# mcu.net
KiCad netlist of a schematic drawn in Altium Designer
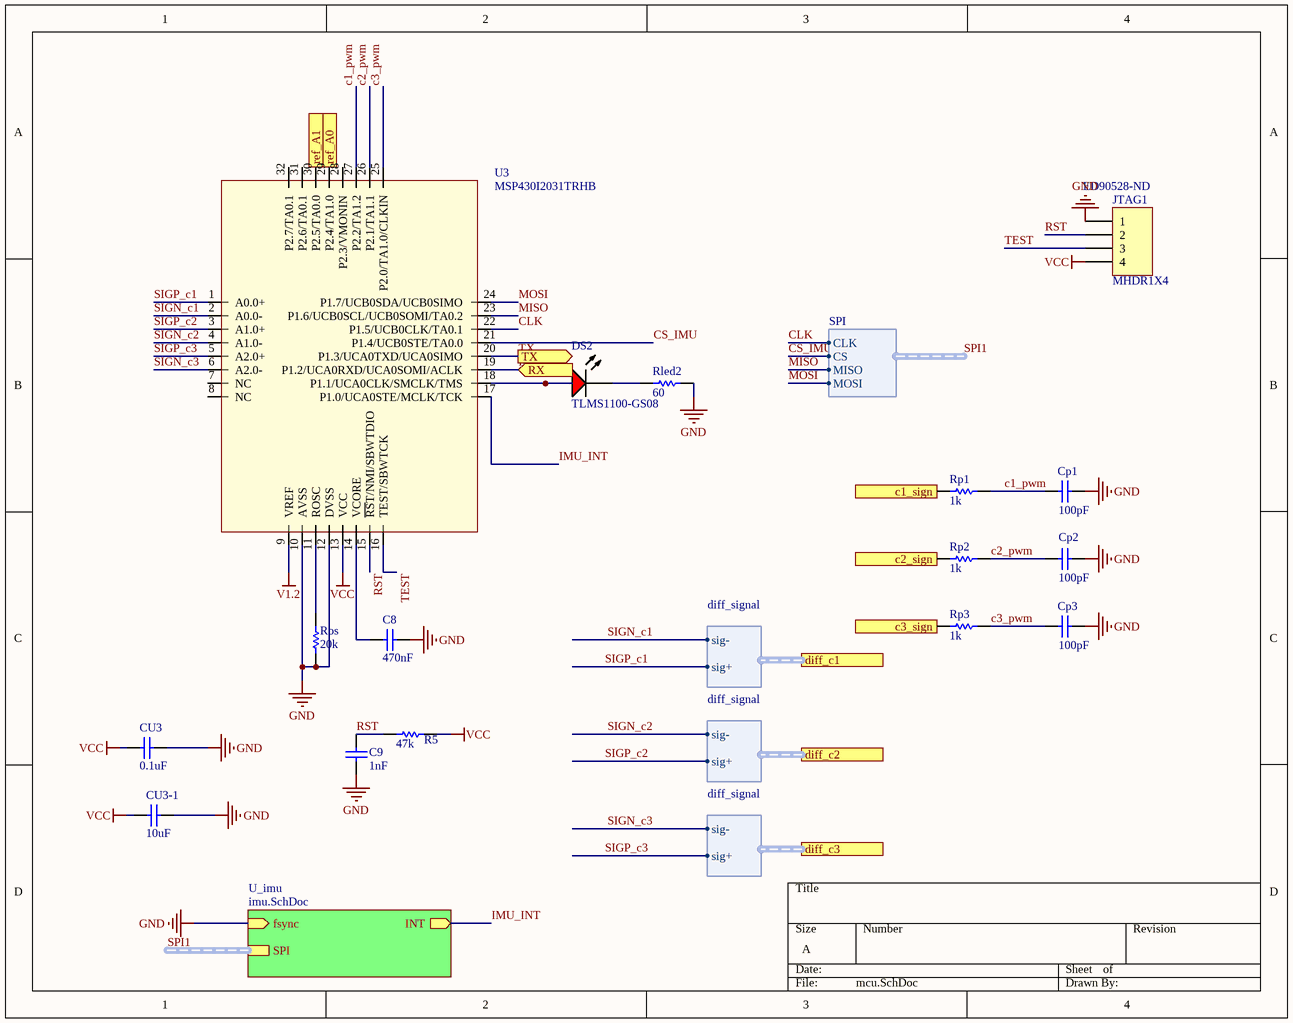
[diagram p0: mcu.SchDoc]

(export (version "E")
  (design (tool "Eeschema 10.0.6"))
  (components
    (comp (ref "C8")
      (value "470nF")
      (footprint "0402")
      (description "Ceramic Capacitor (Surface Mount)")
      (fields (field (name "MANUFACTURER") "Generic Ceramic Chip Cap (TBD)") (field (name "Comment") "Cap"))
      (libsource (lib "maglib") (part "Cap"))
    )
    (comp (ref "C9")
      (value "1nF")
      (footprint "0402")
      (description "Ceramic Capacitor (Surface Mount)")
      (fields (field (name "MANUFACTURER") "Generic Ceramic Chip Cap (TBD)") (field (name "Comment") "Cap"))
      (libsource (lib "maglib") (part "Cap"))
    )
    (comp (ref "Cp1")
      (value "100pF")
      (footprint "0402")
      (description "Ceramic Capacitor (Surface Mount)")
      (fields (field (name "MANUFACTURER") "Generic Ceramic Chip Cap (TBD)") (field (name "Comment") "Cap"))
      (libsource (lib "maglib") (part "Cap"))
    )
    (comp (ref "Cp2")
      (value "100pF")
      (footprint "0402")
      (description "Ceramic Capacitor (Surface Mount)")
      (fields (field (name "MANUFACTURER") "Generic Ceramic Chip Cap (TBD)") (field (name "Comment") "Cap"))
      (libsource (lib "maglib") (part "Cap"))
    )
    (comp (ref "Cp3")
      (value "100pF")
      (footprint "0402")
      (description "Ceramic Capacitor (Surface Mount)")
      (fields (field (name "MANUFACTURER") "Generic Ceramic Chip Cap (TBD)") (field (name "Comment") "Cap"))
      (libsource (lib "maglib") (part "Cap"))
    )
    (comp (ref "CU3")
      (value "0.1uF")
      (footprint "0402")
      (description "Ceramic Capacitor (Surface Mount)")
      (fields (field (name "MANUFACTURER") "Generic Ceramic Chip Cap (TBD)") (field (name "Comment") "Cap"))
      (libsource (lib "maglib") (part "Cap"))
    )
    (comp (ref "CU3-1")
      (value "10uF")
      (footprint "0402")
      (description "Ceramic Capacitor (Surface Mount)")
      (fields (field (name "MANUFACTURER") "Generic Ceramic Chip Cap (TBD)") (field (name "Comment") "Cap"))
      (libsource (lib "maglib") (part "Cap"))
    )
    (comp (ref "DS2")
      (value "TLMS1100-GS08")
      (footprint "VISH-TLMX1100_V")
      (description "LED, RED, 2.1 V, -40 to 100 degC, 2-Pin SMD (0603), RoHS, Tape and Reel")
      (fields (field (name "TOLERANCE") "5%"))
      (libsource (lib "Altium Content Vault") (part "LED-RED-AK-2"))
    )
    (comp (ref "JTAG1")
      (value "MHDR1X4")
      (footprint "MHDR1X4")
      (description "Header, 4-Pin")
      (fields
        (field (name "SUPPLIER PART NUMBER 1") "ED90528-ND")
        (field (name "PUBLISHER") "Altium Limited")
      )
      (libsource (lib "Miscellaneous Connectors") (part "MHDR1X4"))
    )
    (comp (ref "R5")
      (value "47k")
      (footprint "0402")
      (description "Chip Resistor (Surface Mount)")
      (fields (field (name "MANUFACTURER") "Generic Chip Res (TBD)") (field (name "Comment") "Res"))
      (libsource (lib "maglib") (part "Res"))
    )
    (comp (ref "Rled2")
      (value "60")
      (footprint "0402")
      (description "Chip Resistor (Surface Mount)")
      (fields (field (name "MANUFACTURER") "Generic Chip Res (TBD)") (field (name "Comment") "Res"))
      (libsource (lib "maglib") (part "Res"))
    )
    (comp (ref "Ros")
      (value "20k")
      (footprint "0402")
      (description "Chip Resistor (Surface Mount)")
      (fields (field (name "MANUFACTURER") "Generic Chip Res (TBD)") (field (name "Comment") "Res"))
      (libsource (lib "maglib") (part "Res"))
    )
    (comp (ref "Rp1")
      (value "1k")
      (footprint "0402")
      (description "Chip Resistor (Surface Mount)")
      (fields (field (name "MANUFACTURER") "Generic Chip Res (TBD)") (field (name "Comment") "Res"))
      (libsource (lib "maglib") (part "Res"))
    )
    (comp (ref "Rp2")
      (value "1k")
      (footprint "0402")
      (description "Chip Resistor (Surface Mount)")
      (fields (field (name "MANUFACTURER") "Generic Chip Res (TBD)") (field (name "Comment") "Res"))
      (libsource (lib "maglib") (part "Res"))
    )
    (comp (ref "Rp3")
      (value "1k")
      (footprint "0402")
      (description "Chip Resistor (Surface Mount)")
      (fields (field (name "MANUFACTURER") "Generic Chip Res (TBD)") (field (name "Comment") "Res"))
      (libsource (lib "maglib") (part "Res"))
    )
    (comp (ref "U3")
      (value "MSP430I2031TRHB")
      (footprint "QFN50P500X500X100_HS-33N")
      (libsource (lib "maglib") (part "MSP430I2031TRHB"))
    )
  )
  (nets
    (net (code "4") (name "/CLK") (class "Default")
      (node (ref "U3") (pin "22") (pinfunction "P1.5/UCB0CLK/TA0.1_22") (pintype "passive"))
    )
    (net (code "5") (name "/CS_IMU") (class "Default")
      (node (ref "U3") (pin "21") (pinfunction "P1.4/UCB0STE/TA0.0_21") (pintype "passive"))
    )
    (net (code "6") (name "/IMU_INT") (class "Default")
      (node (ref "U3") (pin "17") (pinfunction "P1.0/UCA0STE/MCLK/TCK_17") (pintype "passive"))
    )
    (net (code "7") (name "/MISO") (class "Default")
      (node (ref "U3") (pin "23") (pinfunction "P1.6/UCB0SCL/UCB0SOMI/TA0.2_23") (pintype "passive"))
    )
    (net (code "8") (name "/MOSI") (class "Default")
      (node (ref "U3") (pin "24") (pinfunction "P1.7/UCB0SDA/UCB0SIMO_24") (pintype "passive"))
    )
    (net (code "9") (name "/RST") (class "Default")
      (node (ref "C9") (pin "2") (pinfunction "2_2") (pintype "passive"))
      (node (ref "JTAG1") (pin "2") (pinfunction "2_2") (pintype "passive"))
      (node (ref "R5") (pin "1") (pinfunction "1_1") (pintype "passive"))
      (node (ref "U3") (pin "15") (pinfunction "~{RS}T/NMI/SBWTDIO_15") (pintype "passive"))
    )
    (net (code "10") (name "/RX") (class "Default")
      (node (ref "U3") (pin "19") (pinfunction "P1.2/UCA0RXD/UCA0SOMI/ACLK_19") (pintype "passive"))
    )
    (net (code "11") (name "/SIGN_c1") (class "Default")
      (node (ref "U3") (pin "2") (pinfunction "A0.0-_2") (pintype "passive"))
    )
    (net (code "12") (name "/SIGN_c2") (class "Default")
      (node (ref "U3") (pin "4") (pinfunction "A1.0-_4") (pintype "passive"))
    )
    (net (code "13") (name "/SIGN_c3") (class "Default")
      (node (ref "U3") (pin "6") (pinfunction "A2.0-_6") (pintype "passive"))
    )
    (net (code "14") (name "/SIGP_c1") (class "Default")
      (node (ref "U3") (pin "1") (pinfunction "A0.0+_1") (pintype "passive"))
    )
    (net (code "15") (name "/SIGP_c2") (class "Default")
      (node (ref "U3") (pin "3") (pinfunction "A1.0+_3") (pintype "passive"))
    )
    (net (code "16") (name "/SIGP_c3") (class "Default")
      (node (ref "U3") (pin "5") (pinfunction "A2.0+_5") (pintype "passive"))
    )
    (net (code "18") (name "/TEST") (class "Default")
      (node (ref "JTAG1") (pin "3") (pinfunction "3_3") (pintype "passive"))
      (node (ref "U3") (pin "16") (pinfunction "TEST/SBWTCK_16") (pintype "passive"))
    )
    (net (code "19") (name "/TX") (class "Default")
      (node (ref "U3") (pin "20") (pinfunction "P1.3/UCA0TXD/UCA0SIMO_20") (pintype "passive"))
    )
    (net (code "20") (name "/c1_pwm") (class "Default")
      (node (ref "Cp1") (pin "2") (pinfunction "2_2") (pintype "passive"))
      (node (ref "Rp1") (pin "2") (pinfunction "2_2") (pintype "passive"))
      (node (ref "U3") (pin "27") (pinfunction "P2.2/TA1.2_27") (pintype "passive"))
    )
    (net (code "21") (name "/c1_sign") (class "Default")
      (node (ref "Rp1") (pin "1") (pinfunction "1_1") (pintype "passive"))
    )
    (net (code "22") (name "/c2_pwm") (class "Default")
      (node (ref "Cp2") (pin "2") (pinfunction "2_2") (pintype "passive"))
      (node (ref "Rp2") (pin "2") (pinfunction "2_2") (pintype "passive"))
      (node (ref "U3") (pin "26") (pinfunction "P2.1/TA1.1_26") (pintype "passive"))
    )
    (net (code "23") (name "/c2_sign") (class "Default")
      (node (ref "Rp2") (pin "1") (pinfunction "1_1") (pintype "passive"))
    )
    (net (code "24") (name "/c3_pwm") (class "Default")
      (node (ref "Cp3") (pin "2") (pinfunction "2_2") (pintype "passive"))
      (node (ref "Rp3") (pin "2") (pinfunction "2_2") (pintype "passive"))
      (node (ref "U3") (pin "25") (pinfunction "P2.0/TA1.0/CLKIN_25") (pintype "passive"))
    )
    (net (code "25") (name "/c3_sign") (class "Default")
      (node (ref "Rp3") (pin "1") (pinfunction "1_1") (pintype "passive"))
    )
    (net (code "26") (name "/ref_A0") (class "Default")
      (node (ref "U3") (pin "29") (pinfunction "P2.4/TA1.0_29") (pintype "passive"))
    )
    (net (code "27") (name "/ref_A1") (class "Default")
      (node (ref "U3") (pin "30") (pinfunction "P2.5/TA0.0_30") (pintype "passive"))
    )
    (net (code "30") (name "GND") (class "Default")
      (node (ref "C8") (pin "1") (pinfunction "1_1") (pintype "passive"))
      (node (ref "C9") (pin "1") (pinfunction "1_1") (pintype "passive"))
      (node (ref "CU3") (pin "1") (pinfunction "1_1") (pintype "passive"))
      (node (ref "CU3-1") (pin "1") (pinfunction "1_1") (pintype "passive"))
      (node (ref "Cp1") (pin "1") (pinfunction "1_1") (pintype "passive"))
      (node (ref "Cp2") (pin "1") (pinfunction "1_1") (pintype "passive"))
      (node (ref "Cp3") (pin "1") (pinfunction "1_1") (pintype "passive"))
      (node (ref "JTAG1") (pin "1") (pinfunction "1_1") (pintype "passive"))
      (node (ref "Rled2") (pin "2") (pinfunction "2_2") (pintype "passive"))
      (node (ref "Ros") (pin "1") (pinfunction "1_1") (pintype "passive"))
      (node (ref "U3") (pin "10") (pinfunction "AVSS_10") (pintype "passive"))
      (node (ref "U3") (pin "12") (pinfunction "DVSS_12") (pintype "passive"))
    )
    (net (code "31") (name "Net-(DS2-A)") (class "Default")
      (node (ref "DS2") (pin "1") (pinfunction "A_1") (pintype "passive"))
      (node (ref "U3") (pin "18") (pinfunction "P1.1/UCA0CLK/SMCLK/TMS_18") (pintype "passive"))
    )
    (net (code "32") (name "Net-(DS2-K)") (class "Default")
      (node (ref "DS2") (pin "2") (pinfunction "K_2") (pintype "passive"))
      (node (ref "Rled2") (pin "1") (pinfunction "1_1") (pintype "passive"))
    )
    (net (code "33") (name "Net-(U3-ROSC)") (class "Default")
      (node (ref "Ros") (pin "2") (pinfunction "2_2") (pintype "passive"))
      (node (ref "U3") (pin "11") (pinfunction "ROSC_11") (pintype "passive"))
    )
    (net (code "34") (name "Net-(U3-VCORE)") (class "Default")
      (node (ref "C8") (pin "2") (pinfunction "2_2") (pintype "passive"))
      (node (ref "U3") (pin "14") (pinfunction "VCORE_14") (pintype "passive"))
    )
    (net (code "35") (name "V1.2") (class "Default")
      (node (ref "U3") (pin "9") (pinfunction "VREF_9") (pintype "passive"))
    )
    (net (code "36") (name "VCC") (class "Default")
      (node (ref "CU3") (pin "2") (pinfunction "2_2") (pintype "passive"))
      (node (ref "CU3-1") (pin "2") (pinfunction "2_2") (pintype "passive"))
      (node (ref "JTAG1") (pin "4") (pinfunction "4_4") (pintype "passive"))
      (node (ref "R5") (pin "2") (pinfunction "2_2") (pintype "passive"))
      (node (ref "U3") (pin "13") (pinfunction "VCC_13") (pintype "passive"))
    )
    (net (code "37") (name "unconnected-(U3-NC-Pad7)") (class "Default")
      (node (ref "U3") (pin "7") (pinfunction "NC_7") (pintype "passive"))
    )
    (net (code "38") (name "unconnected-(U3-NC-Pad8)") (class "Default")
      (node (ref "U3") (pin "8") (pinfunction "NC_8") (pintype "passive"))
    )
    (net (code "39") (name "unconnected-(U3-P2.3{slash}VMONIN-Pad28)") (class "Default")
      (node (ref "U3") (pin "28") (pinfunction "P2.3/VMONIN_28") (pintype "passive"))
    )
    (net (code "40") (name "unconnected-(U3-P2.6{slash}TA0.1-Pad31)") (class "Default")
      (node (ref "U3") (pin "31") (pinfunction "P2.6/TA0.1_31") (pintype "passive"))
    )
    (net (code "41") (name "unconnected-(U3-P2.7{slash}TA0.1-Pad32)") (class "Default")
      (node (ref "U3") (pin "32") (pinfunction "P2.7/TA0.1_32") (pintype "passive"))
    )
  )
)
